# 1-Schematic_PixelCard.net
KiCad netlist of a schematic drawn in EasyEDA
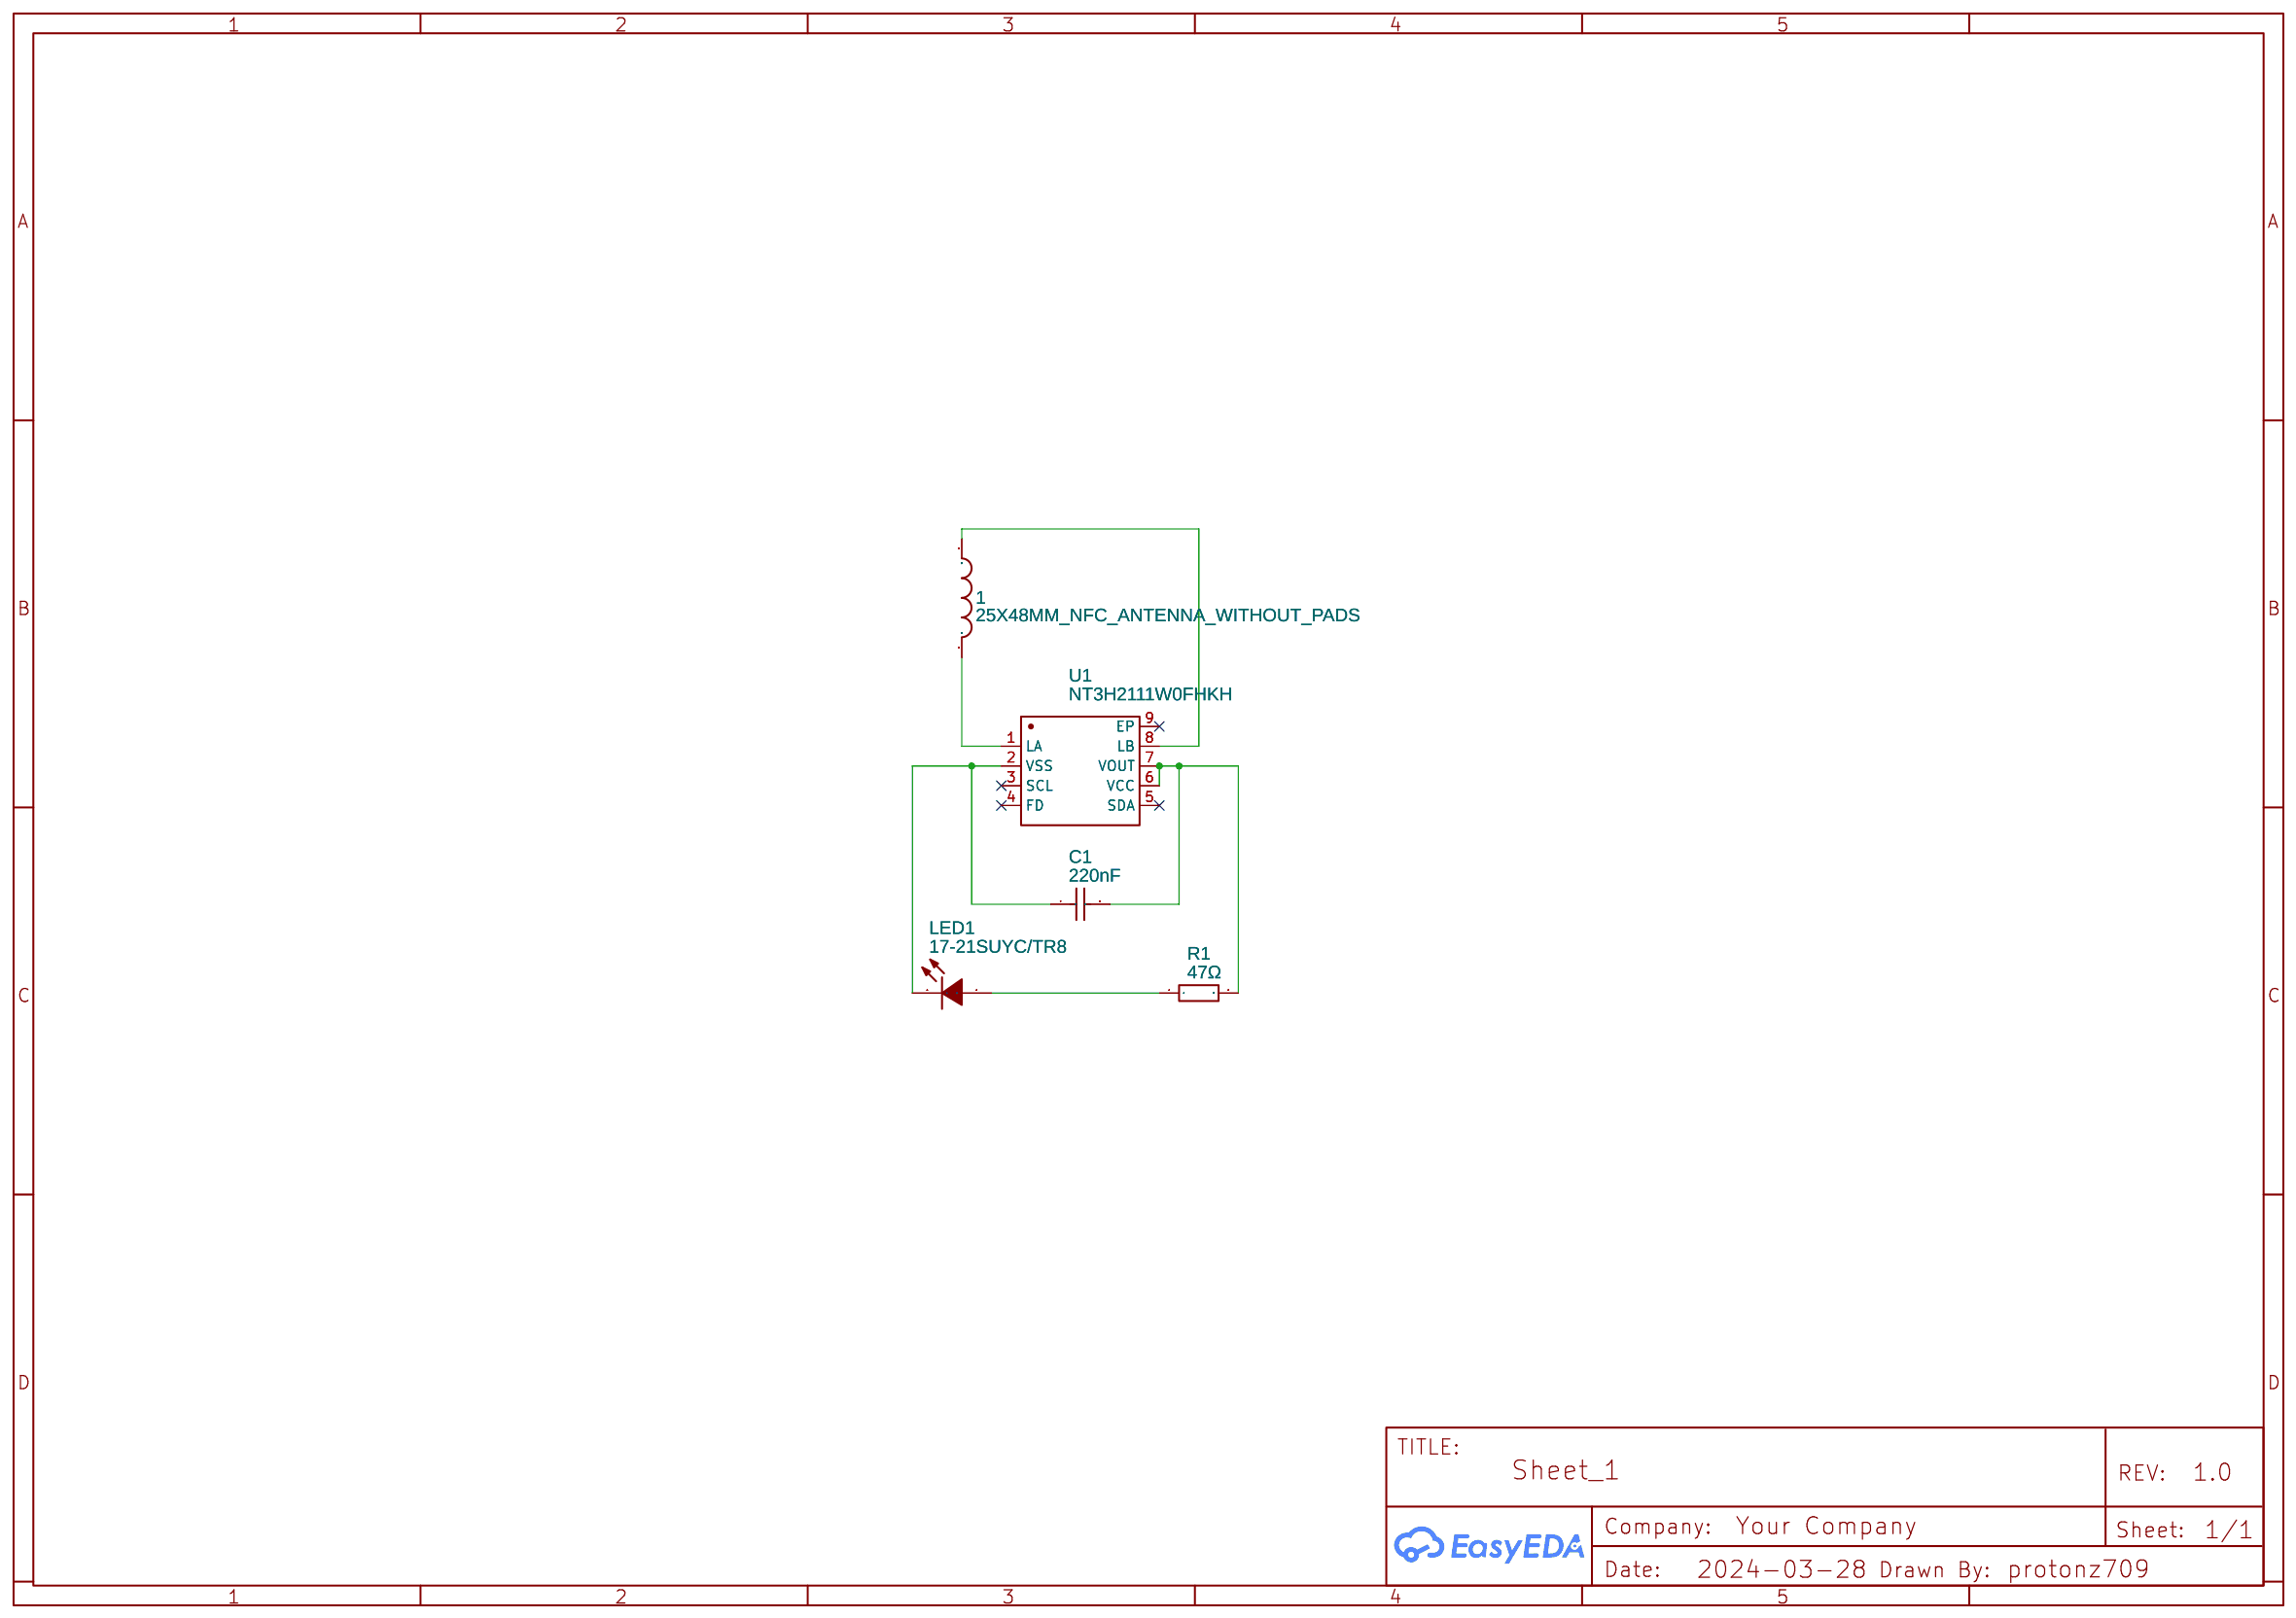
[diagram p0: schematic sheet]

(export (version "E")
  (design (tool "Eeschema 10.0.6"))
  (components
    (comp (ref "1")
      (value "25X48MM_NFC_ANTENNA_WITHOUT_PADS")
      (libsource (lib "") (part "25X48MM_NFC_ANTENNA_WITHOUT_PADS"))
    )
    (comp (ref "C1")
      (value "220nF")
      (fields
        (field (name "Manufacturer Part") "CL10B224KA8NNNC")
        (field (name "Manufacturer") "SAMSUNG(三星)")
      )
      (libsource (lib "") (part "CL10B224KA8NNNC"))
    )
    (comp (ref "LED1")
      (value "17-21SUYC/TR8")
      (fields (field (name "Manufacturer Part") "KT-0805黄灯") (field (name "Manufacturer") "KENTO"))
      (libsource (lib "") (part "17-21SUYC/TR8"))
    )
    (comp (ref "R1")
      (value "47Ω")
      (fields
        (field (name "Manufacturer Part") "0603WAF470JT5E")
        (field (name "Manufacturer") "UNI-ROYAL(厚声)")
      )
      (libsource (lib "") (part "0603WAF470JT5E"))
    )
    (comp (ref "U1")
      (value "NT3H2111W0FHKH")
      (fields (field (name "Manufacturer") "NXP(恩智浦)"))
      (libsource (lib "") (part "NT3H2111W0FHKH"))
    )
  )
  (nets
    (net (code "1") (name "Net-(LED1-+)") (class "Default")
      (node (ref "LED1") (pin "1") (pinfunction "+_1") (pintype "unspecified"))
      (node (ref "R1") (pin "1") (pinfunction "1_1") (pintype "input"))
    )
    (net (code "2") (name "Net-(LED1--)") (class "Default")
      (node (ref "C1") (pin "1") (pinfunction "1_1") (pintype "input"))
      (node (ref "LED1") (pin "2") (pinfunction "-_2") (pintype "unspecified"))
      (node (ref "U1") (pin "2") (pinfunction "VSS_2") (pintype "unspecified"))
    )
    (net (code "3") (name "Net-(U1-LA)") (class "Default")
      (node (ref "1") (pin "P$2") (pinfunction "P$2_P$2") (pintype "bidirectional"))
      (node (ref "U1") (pin "1") (pinfunction "LA_1") (pintype "unspecified"))
    )
    (net (code "4") (name "Net-(U1-LB)") (class "Default")
      (node (ref "1") (pin "P$1") (pinfunction "P$1_P$1") (pintype "bidirectional"))
      (node (ref "U1") (pin "8") (pinfunction "LB_8") (pintype "unspecified"))
    )
    (net (code "5") (name "Net-(U1-VCC)") (class "Default")
      (node (ref "C1") (pin "2") (pinfunction "2_2") (pintype "input"))
      (node (ref "R1") (pin "2") (pinfunction "2_2") (pintype "input"))
      (node (ref "U1") (pin "6") (pinfunction "VCC_6") (pintype "unspecified"))
      (node (ref "U1") (pin "7") (pinfunction "VOUT_7") (pintype "unspecified"))
    )
    (net (code "6") (name "unconnected-(U1-EP-Pad9)") (class "Default")
      (node (ref "U1") (pin "9") (pinfunction "EP_9") (pintype "unspecified+no_connect"))
    )
    (net (code "7") (name "unconnected-(U1-FD-Pad4)") (class "Default")
      (node (ref "U1") (pin "4") (pinfunction "FD_4") (pintype "unspecified+no_connect"))
    )
    (net (code "8") (name "unconnected-(U1-SCL-Pad3)") (class "Default")
      (node (ref "U1") (pin "3") (pinfunction "SCL_3") (pintype "unspecified+no_connect"))
    )
    (net (code "9") (name "unconnected-(U1-SDA-Pad5)") (class "Default")
      (node (ref "U1") (pin "5") (pinfunction "SDA_5") (pintype "unspecified+no_connect"))
    )
  )
)
